# Dispenser.net
KiCad netlist of a schematic drawn in EAGLE
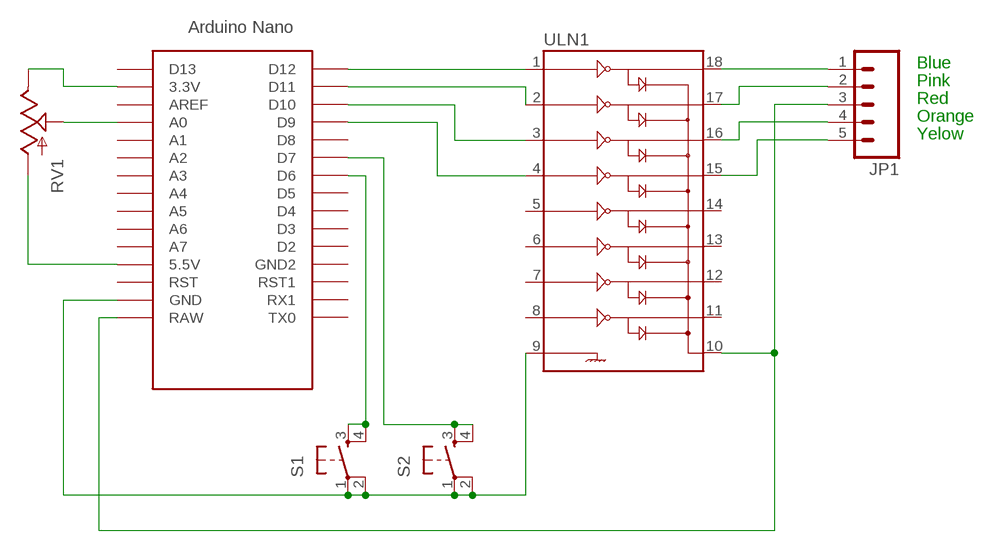
[diagram p0: schematic, sheet 1]

(export (version "E")
  (design (tool "Eeschema 10.0.6"))
  (components
    (comp (ref "JP1")
      (value "M05LOCK")
      (footprint "eagle-import:1X05_LOCK")
      (libsource (lib "eagle-import") (part "M05LOCK"))
    )
    (comp (ref "RV1")
      (value "POT")
      (footprint "eagle-import:ALPS_POT")
      (libsource (lib "eagle-import") (part "POT"))
    )
    (comp (ref "S1")
      (value "TAC_SWITCHPTH")
      (footprint "eagle-import:TACTILE-PTH")
      (libsource (lib "eagle-import") (part "TAC_SWITCHPTH"))
    )
    (comp (ref "S2")
      (value "TAC_SWITCHPTH")
      (footprint "eagle-import:TACTILE-PTH")
      (libsource (lib "eagle-import") (part "TAC_SWITCHPTH"))
    )
    (comp (ref "U$1")
      (value "NANO")
      (footprint "eagle-import:NANO")
      (libsource (lib "eagle-import") (part "NANO"))
    )
    (comp (ref "ULN1")
      (value "ULN2803DIP")
      (footprint "eagle-import:DIL18")
      (libsource (lib "eagle-import") (part "ULN2803DIP"))
    )
  )
  (nets
    (net (code "1") (name "Net-(JP1-Pad1)") (class "Default")
      (node (ref "JP1") (pin "1") (pinfunction "1_1") (pintype "passive"))
      (node (ref "ULN1") (pin "18") (pinfunction "18_18") (pintype "bidirectional"))
    )
    (net (code "2") (name "Net-(JP1-Pad2)") (class "Default")
      (node (ref "JP1") (pin "2") (pinfunction "2_2") (pintype "passive"))
      (node (ref "ULN1") (pin "17") (pinfunction "17_17") (pintype "bidirectional"))
    )
    (net (code "3") (name "Net-(JP1-Pad3)") (class "Default")
      (node (ref "JP1") (pin "3") (pinfunction "3_3") (pintype "passive"))
      (node (ref "U$1") (pin "RAW") (pinfunction "RAW_RAW") (pintype "bidirectional"))
      (node (ref "ULN1") (pin "10") (pinfunction "10_10") (pintype "bidirectional"))
    )
    (net (code "4") (name "Net-(JP1-Pad4)") (class "Default")
      (node (ref "JP1") (pin "4") (pinfunction "4_4") (pintype "passive"))
      (node (ref "ULN1") (pin "16") (pinfunction "16_16") (pintype "bidirectional"))
    )
    (net (code "5") (name "Net-(JP1-Pad5)") (class "Default")
      (node (ref "JP1") (pin "5") (pinfunction "5_5") (pintype "passive"))
      (node (ref "ULN1") (pin "15") (pinfunction "15_15") (pintype "bidirectional"))
    )
    (net (code "6") (name "Net-(RV1-A)") (class "Default")
      (node (ref "RV1") (pin "P$3") (pinfunction "A_P$3") (pintype "passive"))
      (node (ref "U$1") (pin "5V") (pinfunction "5.5V_5V") (pintype "bidirectional"))
    )
    (net (code "7") (name "Net-(RV1-E)") (class "Default")
      (node (ref "RV1") (pin "P$1") (pinfunction "E_P$1") (pintype "passive"))
      (node (ref "U$1") (pin "3.3V") (pinfunction "3.3V_3.3V") (pintype "bidirectional"))
    )
    (net (code "8") (name "Net-(RV1-S)") (class "Default")
      (node (ref "RV1") (pin "P$2") (pinfunction "S_P$2") (pintype "passive"))
      (node (ref "U$1") (pin "A0") (pinfunction "A0_A0") (pintype "bidirectional"))
    )
    (net (code "9") (name "Net-(S1-Pad1)") (class "Default")
      (node (ref "S1") (pin "1") (pinfunction "1_1") (pintype "passive"))
      (node (ref "S1") (pin "2") (pinfunction "2_2") (pintype "passive"))
      (node (ref "S2") (pin "1") (pinfunction "1_1") (pintype "passive"))
      (node (ref "S2") (pin "2") (pinfunction "2_2") (pintype "passive"))
      (node (ref "U$1") (pin "GND") (pinfunction "GND_GND") (pintype "bidirectional"))
      (node (ref "ULN1") (pin "9") (pinfunction "9_9") (pintype "bidirectional"))
    )
    (net (code "10") (name "Net-(S1-Pad3)") (class "Default")
      (node (ref "S1") (pin "3") (pinfunction "3_3") (pintype "passive"))
      (node (ref "S1") (pin "4") (pinfunction "4_4") (pintype "passive"))
      (node (ref "U$1") (pin "D6") (pinfunction "D6_D6") (pintype "bidirectional"))
    )
    (net (code "11") (name "Net-(S2-Pad3)") (class "Default")
      (node (ref "S2") (pin "3") (pinfunction "3_3") (pintype "passive"))
      (node (ref "S2") (pin "4") (pinfunction "4_4") (pintype "passive"))
      (node (ref "U$1") (pin "D7") (pinfunction "D7_D7") (pintype "bidirectional"))
    )
    (net (code "12") (name "Net-(U$1-PadD9)") (class "Default")
      (node (ref "U$1") (pin "D9") (pinfunction "D9_D9") (pintype "bidirectional"))
      (node (ref "ULN1") (pin "4") (pinfunction "4_4") (pintype "bidirectional"))
    )
    (net (code "13") (name "Net-(U$1-PadD10)") (class "Default")
      (node (ref "U$1") (pin "D10") (pinfunction "D10_D10") (pintype "bidirectional"))
      (node (ref "ULN1") (pin "3") (pinfunction "3_3") (pintype "bidirectional"))
    )
    (net (code "14") (name "Net-(U$1-PadD11)") (class "Default")
      (node (ref "U$1") (pin "D11") (pinfunction "D11_D11") (pintype "bidirectional"))
      (node (ref "ULN1") (pin "2") (pinfunction "2_2") (pintype "bidirectional"))
    )
    (net (code "15") (name "Net-(U$1-PadD12)") (class "Default")
      (node (ref "U$1") (pin "D12") (pinfunction "D12_D12") (pintype "bidirectional"))
      (node (ref "ULN1") (pin "1") (pinfunction "1_1") (pintype "bidirectional"))
    )
    (net (code "16") (name "unconnected-(U$1-GND2-PadGND1)") (class "Default")
      (node (ref "U$1") (pin "GND1") (pinfunction "GND2_GND1") (pintype "bidirectional"))
    )
    (net (code "17") (name "unconnected-(U$1-PadA1)") (class "Default")
      (node (ref "U$1") (pin "A1") (pinfunction "A1_A1") (pintype "bidirectional"))
    )
    (net (code "18") (name "unconnected-(U$1-PadA2)") (class "Default")
      (node (ref "U$1") (pin "A2") (pinfunction "A2_A2") (pintype "bidirectional"))
    )
    (net (code "19") (name "unconnected-(U$1-PadA3)") (class "Default")
      (node (ref "U$1") (pin "A3") (pinfunction "A3_A3") (pintype "bidirectional"))
    )
    (net (code "20") (name "unconnected-(U$1-PadA4)") (class "Default")
      (node (ref "U$1") (pin "A4") (pinfunction "A4_A4") (pintype "bidirectional"))
    )
    (net (code "21") (name "unconnected-(U$1-PadA5)") (class "Default")
      (node (ref "U$1") (pin "A5") (pinfunction "A5_A5") (pintype "bidirectional"))
    )
    (net (code "22") (name "unconnected-(U$1-PadA6)") (class "Default")
      (node (ref "U$1") (pin "A6") (pinfunction "A6_A6") (pintype "bidirectional"))
    )
    (net (code "23") (name "unconnected-(U$1-PadA7)") (class "Default")
      (node (ref "U$1") (pin "A7") (pinfunction "A7_A7") (pintype "bidirectional"))
    )
    (net (code "24") (name "unconnected-(U$1-PadAREF)") (class "Default")
      (node (ref "U$1") (pin "AREF") (pinfunction "AREF_AREF") (pintype "bidirectional"))
    )
    (net (code "25") (name "unconnected-(U$1-PadD2)") (class "Default")
      (node (ref "U$1") (pin "D2") (pinfunction "D2_D2") (pintype "bidirectional"))
    )
    (net (code "26") (name "unconnected-(U$1-PadD3)") (class "Default")
      (node (ref "U$1") (pin "D3") (pinfunction "D3_D3") (pintype "bidirectional"))
    )
    (net (code "27") (name "unconnected-(U$1-PadD4)") (class "Default")
      (node (ref "U$1") (pin "D4") (pinfunction "D4_D4") (pintype "bidirectional"))
    )
    (net (code "28") (name "unconnected-(U$1-PadD5)") (class "Default")
      (node (ref "U$1") (pin "D5") (pinfunction "D5_D5") (pintype "bidirectional"))
    )
    (net (code "29") (name "unconnected-(U$1-PadD8)") (class "Default")
      (node (ref "U$1") (pin "D8") (pinfunction "D8_D8") (pintype "bidirectional"))
    )
    (net (code "30") (name "unconnected-(U$1-PadD13)") (class "Default")
      (node (ref "U$1") (pin "D13") (pinfunction "D13_D13") (pintype "bidirectional"))
    )
    (net (code "31") (name "unconnected-(U$1-PadICSP1)") (class "Default")
      (node (ref "U$1") (pin "ICSP1") (pinfunction "ICSP1_ICSP1") (pintype "bidirectional"))
    )
    (net (code "32") (name "unconnected-(U$1-PadICSP2)") (class "Default")
      (node (ref "U$1") (pin "ICSP2") (pinfunction "ICSP2_ICSP2") (pintype "bidirectional"))
    )
    (net (code "33") (name "unconnected-(U$1-PadICSP3)") (class "Default")
      (node (ref "U$1") (pin "ICSP3") (pinfunction "ICSP3_ICSP3") (pintype "bidirectional"))
    )
    (net (code "34") (name "unconnected-(U$1-PadICSP4)") (class "Default")
      (node (ref "U$1") (pin "ICSP4") (pinfunction "ICSP4_ICSP4") (pintype "bidirectional"))
    )
    (net (code "35") (name "unconnected-(U$1-PadICSP5)") (class "Default")
      (node (ref "U$1") (pin "ICSP5") (pinfunction "ICSP5_ICSP5") (pintype "bidirectional"))
    )
    (net (code "36") (name "unconnected-(U$1-PadICSP6)") (class "Default")
      (node (ref "U$1") (pin "ICSP6") (pinfunction "ICSP6_ICSP6") (pintype "bidirectional"))
    )
    (net (code "37") (name "unconnected-(U$1-PadRST)") (class "Default")
      (node (ref "U$1") (pin "RST") (pinfunction "RST_RST") (pintype "bidirectional"))
    )
    (net (code "38") (name "unconnected-(U$1-PadRST1)") (class "Default")
      (node (ref "U$1") (pin "RST1") (pinfunction "RST1_RST1") (pintype "bidirectional"))
    )
    (net (code "39") (name "unconnected-(U$1-PadRX1)") (class "Default")
      (node (ref "U$1") (pin "RX1") (pinfunction "RX1_RX1") (pintype "bidirectional"))
    )
    (net (code "40") (name "unconnected-(U$1-PadTX0)") (class "Default")
      (node (ref "U$1") (pin "TX0") (pinfunction "TX0_TX0") (pintype "bidirectional"))
    )
    (net (code "41") (name "unconnected-(ULN1-Pad5)") (class "Default")
      (node (ref "ULN1") (pin "5") (pinfunction "5_5") (pintype "bidirectional"))
    )
    (net (code "42") (name "unconnected-(ULN1-Pad6)") (class "Default")
      (node (ref "ULN1") (pin "6") (pinfunction "6_6") (pintype "bidirectional"))
    )
    (net (code "43") (name "unconnected-(ULN1-Pad7)") (class "Default")
      (node (ref "ULN1") (pin "7") (pinfunction "7_7") (pintype "bidirectional"))
    )
    (net (code "44") (name "unconnected-(ULN1-Pad8)") (class "Default")
      (node (ref "ULN1") (pin "8") (pinfunction "8_8") (pintype "bidirectional"))
    )
    (net (code "45") (name "unconnected-(ULN1-Pad11)") (class "Default")
      (node (ref "ULN1") (pin "11") (pinfunction "11_11") (pintype "bidirectional"))
    )
    (net (code "46") (name "unconnected-(ULN1-Pad12)") (class "Default")
      (node (ref "ULN1") (pin "12") (pinfunction "12_12") (pintype "bidirectional"))
    )
    (net (code "47") (name "unconnected-(ULN1-Pad13)") (class "Default")
      (node (ref "ULN1") (pin "13") (pinfunction "13_13") (pintype "bidirectional"))
    )
    (net (code "48") (name "unconnected-(ULN1-Pad14)") (class "Default")
      (node (ref "ULN1") (pin "14") (pinfunction "14_14") (pintype "bidirectional"))
    )
  )
)
